# ballistic-amp.net
KiCad netlist of a schematic drawn in EAGLE
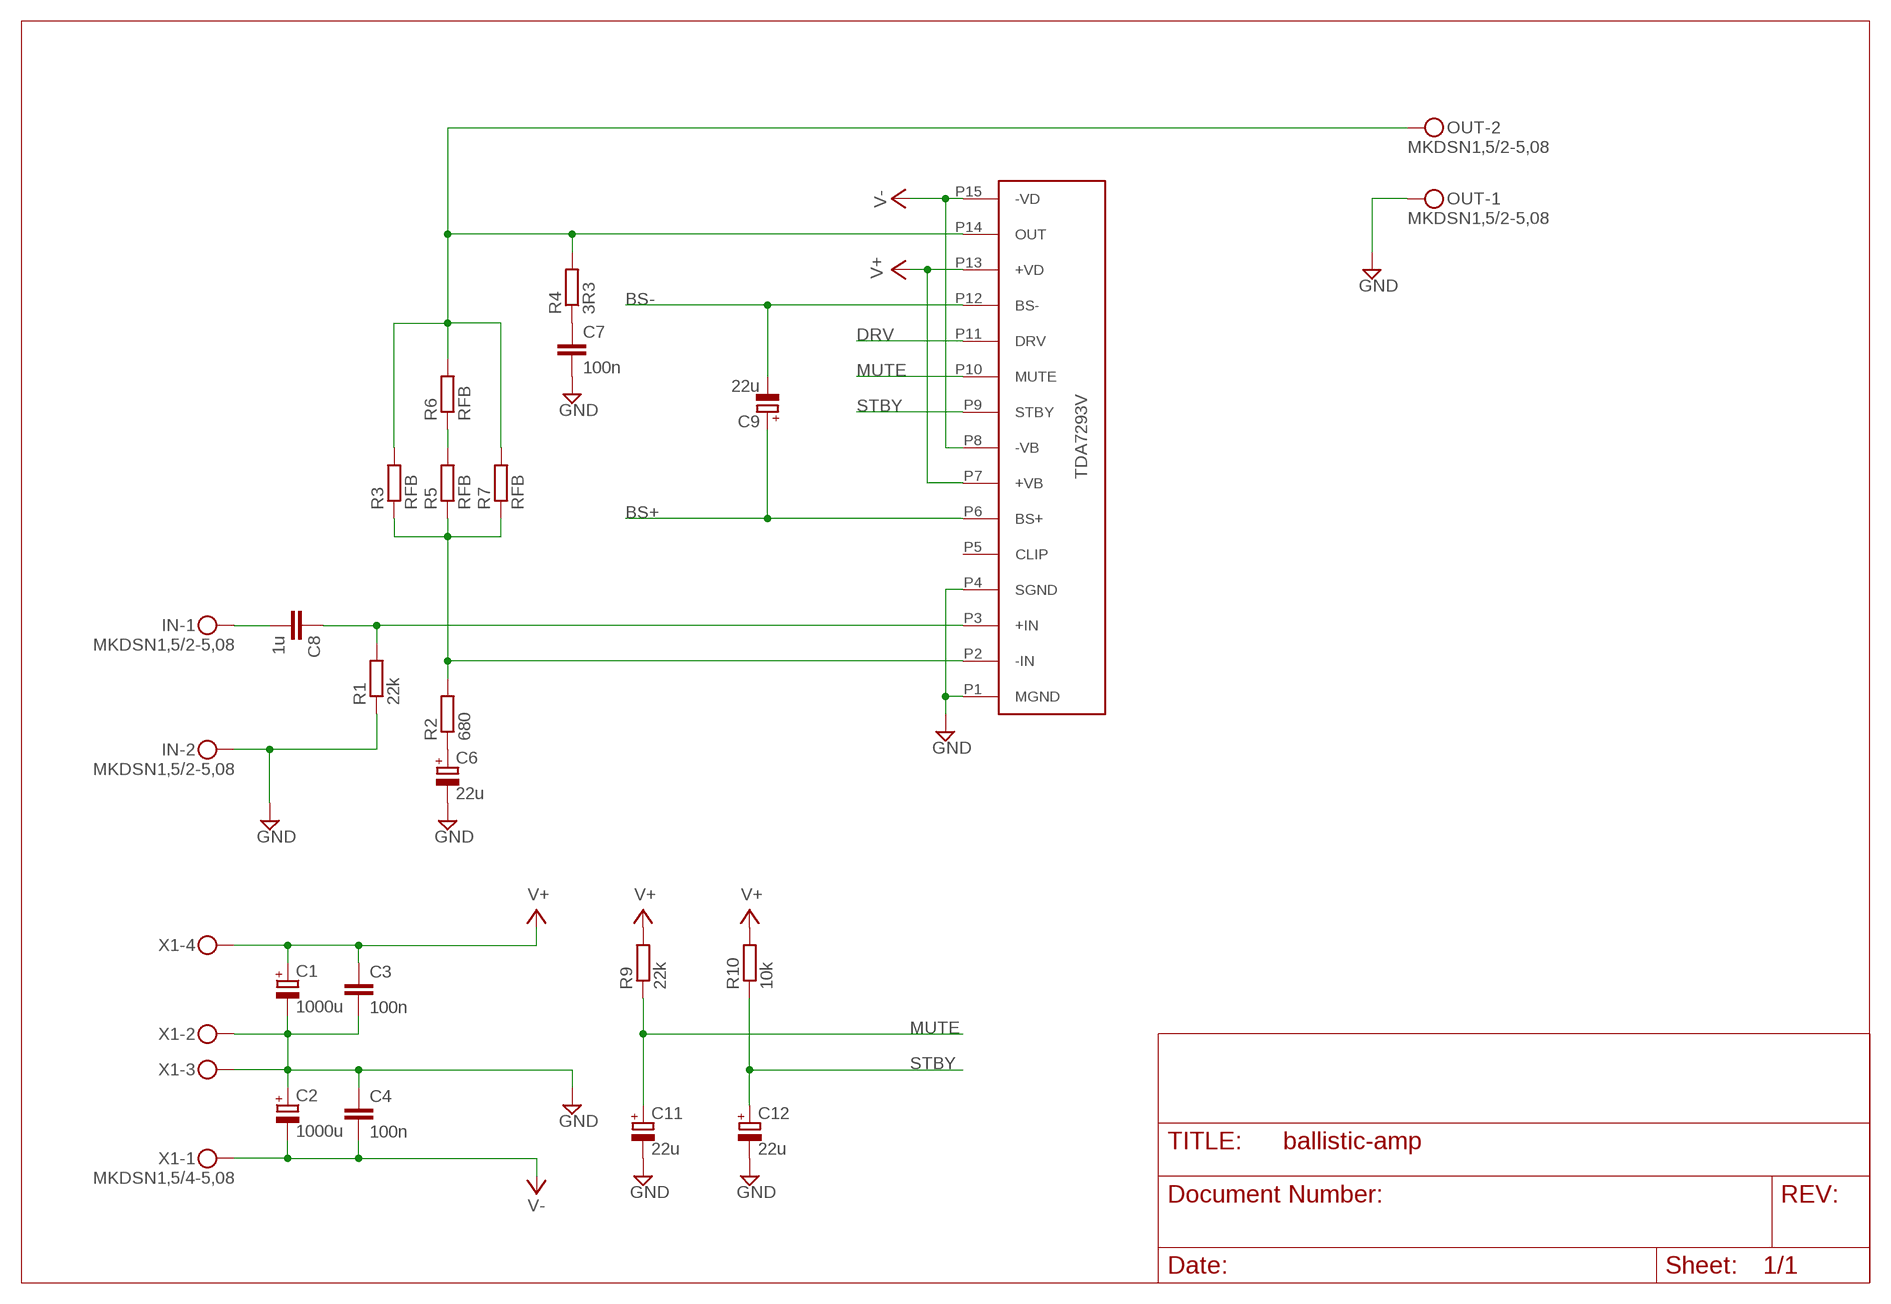
[diagram p0: schematic, sheet 1]

(export (version "E")
  (design (tool "Eeschema 10.0.6"))
  (components
    (comp (ref "C1")
      (value "1000u")
      (footprint "eagle-import:E7,5-18")
      (libsource (lib "eagle-import") (part "CPOL-EUE7.5-18"))
    )
    (comp (ref "C2")
      (value "1000u")
      (footprint "eagle-import:E7,5-18")
      (libsource (lib "eagle-import") (part "CPOL-EUE7.5-18"))
    )
    (comp (ref "C3")
      (value "100n")
      (footprint "eagle-import:C050-025X075")
      (libsource (lib "eagle-import") (part "C-EU050-025X075"))
    )
    (comp (ref "C4")
      (value "100n")
      (footprint "eagle-import:C050-025X075")
      (libsource (lib "eagle-import") (part "C-EU050-025X075"))
    )
    (comp (ref "C6")
      (value "22u")
      (footprint "eagle-import:E5-10,5")
      (libsource (lib "eagle-import") (part "CPOL-EUE5-10.5"))
    )
    (comp (ref "C7")
      (value "100n")
      (footprint "eagle-import:C050-025X075")
      (libsource (lib "eagle-import") (part "C-EU050-025X075"))
    )
    (comp (ref "C8")
      (value "1u")
      (footprint "eagle-import:C1210")
      (libsource (lib "eagle-import") (part "C-EUC1210"))
    )
    (comp (ref "C9")
      (value "22u")
      (footprint "eagle-import:E5-10,5")
      (libsource (lib "eagle-import") (part "CPOL-EUE5-10.5"))
    )
    (comp (ref "C11")
      (value "22u")
      (footprint "eagle-import:UD-6,3X7,7_NICHICON")
      (libsource (lib "eagle-import") (part "CPOL-EUUD-6,3X7,7"))
    )
    (comp (ref "C12")
      (value "22u")
      (footprint "eagle-import:UD-6,3X7,7_NICHICON")
      (libsource (lib "eagle-import") (part "CPOL-EUUD-6,3X7,7"))
    )
    (comp (ref "IN")
      (value "MKDSN1,5/2-5,08")
      (footprint "eagle-import:MKDSN1,5_2-5,08")
      (libsource (lib "eagle-import") (part "MKDSN1,5/2-5,08"))
    )
    (comp (ref "OUT")
      (value "MKDSN1,5/2-5,08")
      (footprint "eagle-import:MKDSN1,5_2-5,08")
      (libsource (lib "eagle-import") (part "MKDSN1,5/2-5,08"))
    )
    (comp (ref "R1")
      (value "22k")
      (footprint "eagle-import:0207_10")
      (libsource (lib "eagle-import") (part "R-EU_0207/10"))
    )
    (comp (ref "R2")
      (value "680")
      (footprint "eagle-import:0207_10")
      (libsource (lib "eagle-import") (part "R-EU_0207/10"))
    )
    (comp (ref "R3")
      (value "RFB")
      (footprint "eagle-import:0207_10")
      (libsource (lib "eagle-import") (part "R-EU_0207/10"))
    )
    (comp (ref "R4")
      (value "3R3")
      (footprint "eagle-import:R2512")
      (libsource (lib "eagle-import") (part "R-EU_R2512"))
    )
    (comp (ref "R5")
      (value "RFB")
      (footprint "eagle-import:0207_10")
      (libsource (lib "eagle-import") (part "R-EU_0207/10"))
    )
    (comp (ref "R6")
      (value "RFB")
      (footprint "eagle-import:0207_10")
      (libsource (lib "eagle-import") (part "R-EU_0207/10"))
    )
    (comp (ref "R7")
      (value "RFB")
      (footprint "eagle-import:0207_10")
      (libsource (lib "eagle-import") (part "R-EU_0207/10"))
    )
    (comp (ref "R9")
      (value "22k")
      (footprint "eagle-import:0207_10")
      (libsource (lib "eagle-import") (part "R-EU_0207/10"))
    )
    (comp (ref "R10")
      (value "10k")
      (footprint "eagle-import:0207_10")
      (libsource (lib "eagle-import") (part "R-EU_0207/10"))
    )
    (comp (ref "U$1")
      (value "TDA7293V")
      (footprint "eagle-import:TDA7293V")
      (libsource (lib "eagle-import") (part "TDA7293V"))
    )
    (comp (ref "X1")
      (value "MKDSN1,5/4-5,08")
      (footprint "eagle-import:MKDSN1,5_4-5,08")
      (libsource (lib "eagle-import") (part "MKDSN1,5/4-5,08"))
    )
  )
  (nets
    (net (code "1") (name "/BS+") (class "Default")
      (node (ref "C9") (pin "+") (pinfunction "+_+") (pintype "passive"))
      (node (ref "U$1") (pin "P6") (pinfunction "BS+_P6") (pintype "bidirectional"))
    )
    (net (code "2") (name "/BS-") (class "Default")
      (node (ref "C9") (pin "-") (pinfunction "-_-") (pintype "passive"))
      (node (ref "U$1") (pin "P12") (pinfunction "BS-_P12") (pintype "bidirectional"))
    )
    (net (code "3") (name "/DRV") (class "Default")
      (node (ref "U$1") (pin "P11") (pinfunction "DRV_P11") (pintype "bidirectional"))
    )
    (net (code "4") (name "/MUTE") (class "Default")
      (node (ref "C11") (pin "+") (pinfunction "+_+") (pintype "passive"))
      (node (ref "R9") (pin "1") (pinfunction "1_1") (pintype "passive"))
      (node (ref "U$1") (pin "P10") (pinfunction "MUTE_P10") (pintype "bidirectional"))
    )
    (net (code "5") (name "/STBY") (class "Default")
      (node (ref "C12") (pin "+") (pinfunction "+_+") (pintype "passive"))
      (node (ref "R10") (pin "1") (pinfunction "1_1") (pintype "passive"))
      (node (ref "U$1") (pin "P9") (pinfunction "STBY_P9") (pintype "bidirectional"))
    )
    (net (code "6") (name "GND") (class "Default")
      (node (ref "C1") (pin "-") (pinfunction "-_-") (pintype "passive"))
      (node (ref "C11") (pin "-") (pinfunction "-_-") (pintype "passive"))
      (node (ref "C12") (pin "-") (pinfunction "-_-") (pintype "passive"))
      (node (ref "C2") (pin "+") (pinfunction "+_+") (pintype "passive"))
      (node (ref "C3") (pin "2") (pinfunction "2_2") (pintype "passive"))
      (node (ref "C4") (pin "1") (pinfunction "1_1") (pintype "passive"))
      (node (ref "C6") (pin "-") (pinfunction "-_-") (pintype "passive"))
      (node (ref "C7") (pin "2") (pinfunction "2_2") (pintype "passive"))
      (node (ref "IN") (pin "2") (pinfunction "KL_2") (pintype "passive"))
      (node (ref "OUT") (pin "1") (pinfunction "KL_1") (pintype "passive"))
      (node (ref "R1") (pin "1") (pinfunction "1_1") (pintype "passive"))
      (node (ref "U$1") (pin "P1") (pinfunction "MGND_P1") (pintype "bidirectional"))
      (node (ref "U$1") (pin "P4") (pinfunction "SGND_P4") (pintype "bidirectional"))
      (node (ref "X1") (pin "2") (pinfunction "KL_2") (pintype "passive"))
      (node (ref "X1") (pin "3") (pinfunction "KL_3") (pintype "passive"))
    )
    (net (code "7") (name "Net-(C6-Pad+)") (class "Default")
      (node (ref "C6") (pin "+") (pinfunction "+_+") (pintype "passive"))
      (node (ref "R2") (pin "1") (pinfunction "1_1") (pintype "passive"))
    )
    (net (code "8") (name "Net-(C7-Pad1)") (class "Default")
      (node (ref "C7") (pin "1") (pinfunction "1_1") (pintype "passive"))
      (node (ref "R4") (pin "1") (pinfunction "1_1") (pintype "passive"))
    )
    (net (code "9") (name "Net-(INA-KL)") (class "Default")
      (node (ref "C8") (pin "2") (pinfunction "2_2") (pintype "passive"))
      (node (ref "IN") (pin "1") (pinfunction "KL_1") (pintype "passive"))
    )
    (net (code "10") (name "Net-(OUTB-KL)") (class "Default")
      (node (ref "OUT") (pin "2") (pinfunction "KL_2") (pintype "passive"))
      (node (ref "R3") (pin "2") (pinfunction "2_2") (pintype "passive"))
      (node (ref "R4") (pin "2") (pinfunction "2_2") (pintype "passive"))
      (node (ref "R6") (pin "2") (pinfunction "2_2") (pintype "passive"))
      (node (ref "R7") (pin "2") (pinfunction "2_2") (pintype "passive"))
      (node (ref "U$1") (pin "P14") (pinfunction "OUT_P14") (pintype "bidirectional"))
    )
    (net (code "11") (name "Net-(R5-Pad2)") (class "Default")
      (node (ref "R5") (pin "2") (pinfunction "2_2") (pintype "passive"))
      (node (ref "R6") (pin "1") (pinfunction "1_1") (pintype "passive"))
    )
    (net (code "12") (name "Net-(U$1-+IN)") (class "Default")
      (node (ref "C8") (pin "1") (pinfunction "1_1") (pintype "passive"))
      (node (ref "R1") (pin "2") (pinfunction "2_2") (pintype "passive"))
      (node (ref "U$1") (pin "P3") (pinfunction "+IN_P3") (pintype "bidirectional"))
    )
    (net (code "13") (name "Net-(U$1--IN)") (class "Default")
      (node (ref "R2") (pin "2") (pinfunction "2_2") (pintype "passive"))
      (node (ref "R3") (pin "1") (pinfunction "1_1") (pintype "passive"))
      (node (ref "R5") (pin "1") (pinfunction "1_1") (pintype "passive"))
      (node (ref "R7") (pin "1") (pinfunction "1_1") (pintype "passive"))
      (node (ref "U$1") (pin "P2") (pinfunction "-IN_P2") (pintype "bidirectional"))
    )
    (net (code "14") (name "V+") (class "Default")
      (node (ref "C1") (pin "+") (pinfunction "+_+") (pintype "passive"))
      (node (ref "C3") (pin "1") (pinfunction "1_1") (pintype "passive"))
      (node (ref "R10") (pin "2") (pinfunction "2_2") (pintype "passive"))
      (node (ref "R9") (pin "2") (pinfunction "2_2") (pintype "passive"))
      (node (ref "U$1") (pin "P13") (pinfunction "+VD_P13") (pintype "bidirectional"))
      (node (ref "U$1") (pin "P7") (pinfunction "+VB_P7") (pintype "bidirectional"))
      (node (ref "X1") (pin "4") (pinfunction "KL_4") (pintype "passive"))
    )
    (net (code "15") (name "V-") (class "Default")
      (node (ref "C2") (pin "-") (pinfunction "-_-") (pintype "passive"))
      (node (ref "C4") (pin "2") (pinfunction "2_2") (pintype "passive"))
      (node (ref "U$1") (pin "P15") (pinfunction "-VD_P15") (pintype "bidirectional"))
      (node (ref "U$1") (pin "P8") (pinfunction "-VB_P8") (pintype "bidirectional"))
      (node (ref "X1") (pin "1") (pinfunction "KL_1") (pintype "passive"))
    )
    (net (code "16") (name "unconnected-(U$1-CLIP-PadP5)") (class "Default")
      (node (ref "U$1") (pin "P5") (pinfunction "CLIP_P5") (pintype "bidirectional"))
    )
  )
)
